# 05_Power.net
KiCad netlist of a schematic drawn in Altium Designer
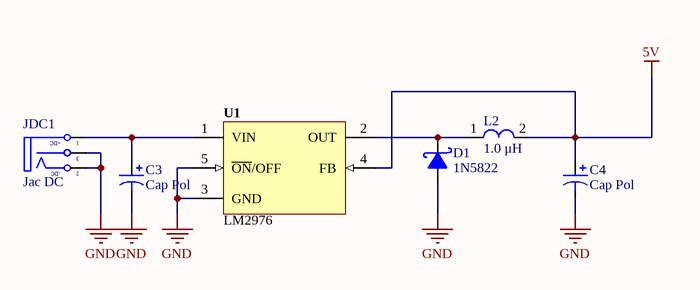
[diagram p0: [05] Power.SchDoc]

(export (version "E")
  (design (tool "Eeschema 10.0.6"))
  (components
    (comp (ref "C3")
      (value "Cap Pol")
      (footprint "C3MM")
      (description "Polarized Capacitor (Axial)")
      (fields (field (name "PUBLISHER") "Altium Limited"))
      (libsource (lib "My Library") (part "Cap Pol"))
    )
    (comp (ref "C4")
      (value "Cap Pol")
      (footprint "C3MM")
      (description "Polarized Capacitor (Axial)")
      (fields (field (name "PUBLISHER") "Altium Limited"))
      (libsource (lib "My Library") (part "Cap Pol"))
    )
    (comp (ref "D1")
      (value "1N5822")
      (footprint "DIO-SMD-123")
      (description "Schottky Rectifiers")
      (libsource (lib "My Library") (part "1N5822"))
    )
    (comp (ref "JDC1")
      (value "Jac DC")
      (footprint "DC-IN")
      (description "Jac DC input")
      (libsource (lib "My Library") (part "DCIN"))
    )
    (comp (ref "L2")
      (value "1.0 μH")
      (footprint "L-SMD-M-7.3x4.5")
      (fields
        (field (name "PARTNO") "78477010")
        (field (name "MANUFACTURER") "Wurth Elektronik")
        (field (name "CREATED BY") "Baojun Chen")
      )
      (libsource (lib "My Library") (part "L-SMD-1"))
    )
    (comp (ref "U1") (value "LM2976") (footprint "TO263") (libsource (lib "My Library") (part "LM2596")))
  )
  (nets
    (net (code "1") (name "5V") (class "Default")
      (node (ref "C4") (pin "1") (pinfunction "1_1") (pintype "passive"))
      (node (ref "L2") (pin "2") (pinfunction "2_2") (pintype "passive"))
      (node (ref "U1") (pin "4") (pinfunction "FB_4") (pintype "input"))
    )
    (net (code "2") (name "GND") (class "Default")
      (node (ref "C3") (pin "2") (pinfunction "2_2") (pintype "passive"))
      (node (ref "C4") (pin "2") (pinfunction "2_2") (pintype "passive"))
      (node (ref "D1") (pin "1") (pinfunction "A_1") (pintype "passive"))
      (node (ref "JDC1") (pin "2") (pinfunction "TN_2") (pintype "passive"))
      (node (ref "JDC1") (pin "3") (pinfunction "S_3") (pintype "power_in"))
      (node (ref "U1") (pin "3") (pinfunction "GND_3") (pintype "power_in"))
      (node (ref "U1") (pin "5") (pinfunction "~{ON}/OFF_5") (pintype "input"))
    )
    (net (code "3") (name "Net-(D1-K)") (class "Default")
      (node (ref "D1") (pin "2") (pinfunction "K_2") (pintype "passive"))
      (node (ref "L2") (pin "1") (pinfunction "1_1") (pintype "passive"))
      (node (ref "U1") (pin "2") (pinfunction "OUT_2") (pintype "power_in"))
    )
    (net (code "4") (name "Net-(JDC1-T)") (class "Default")
      (node (ref "C3") (pin "1") (pinfunction "1_1") (pintype "passive"))
      (node (ref "JDC1") (pin "1") (pinfunction "T_1") (pintype "passive"))
      (node (ref "U1") (pin "1") (pinfunction "VIN_1") (pintype "power_in"))
    )
  )
)
